# BTRelays.net
KiCad netlist of a schematic drawn in EAGLE
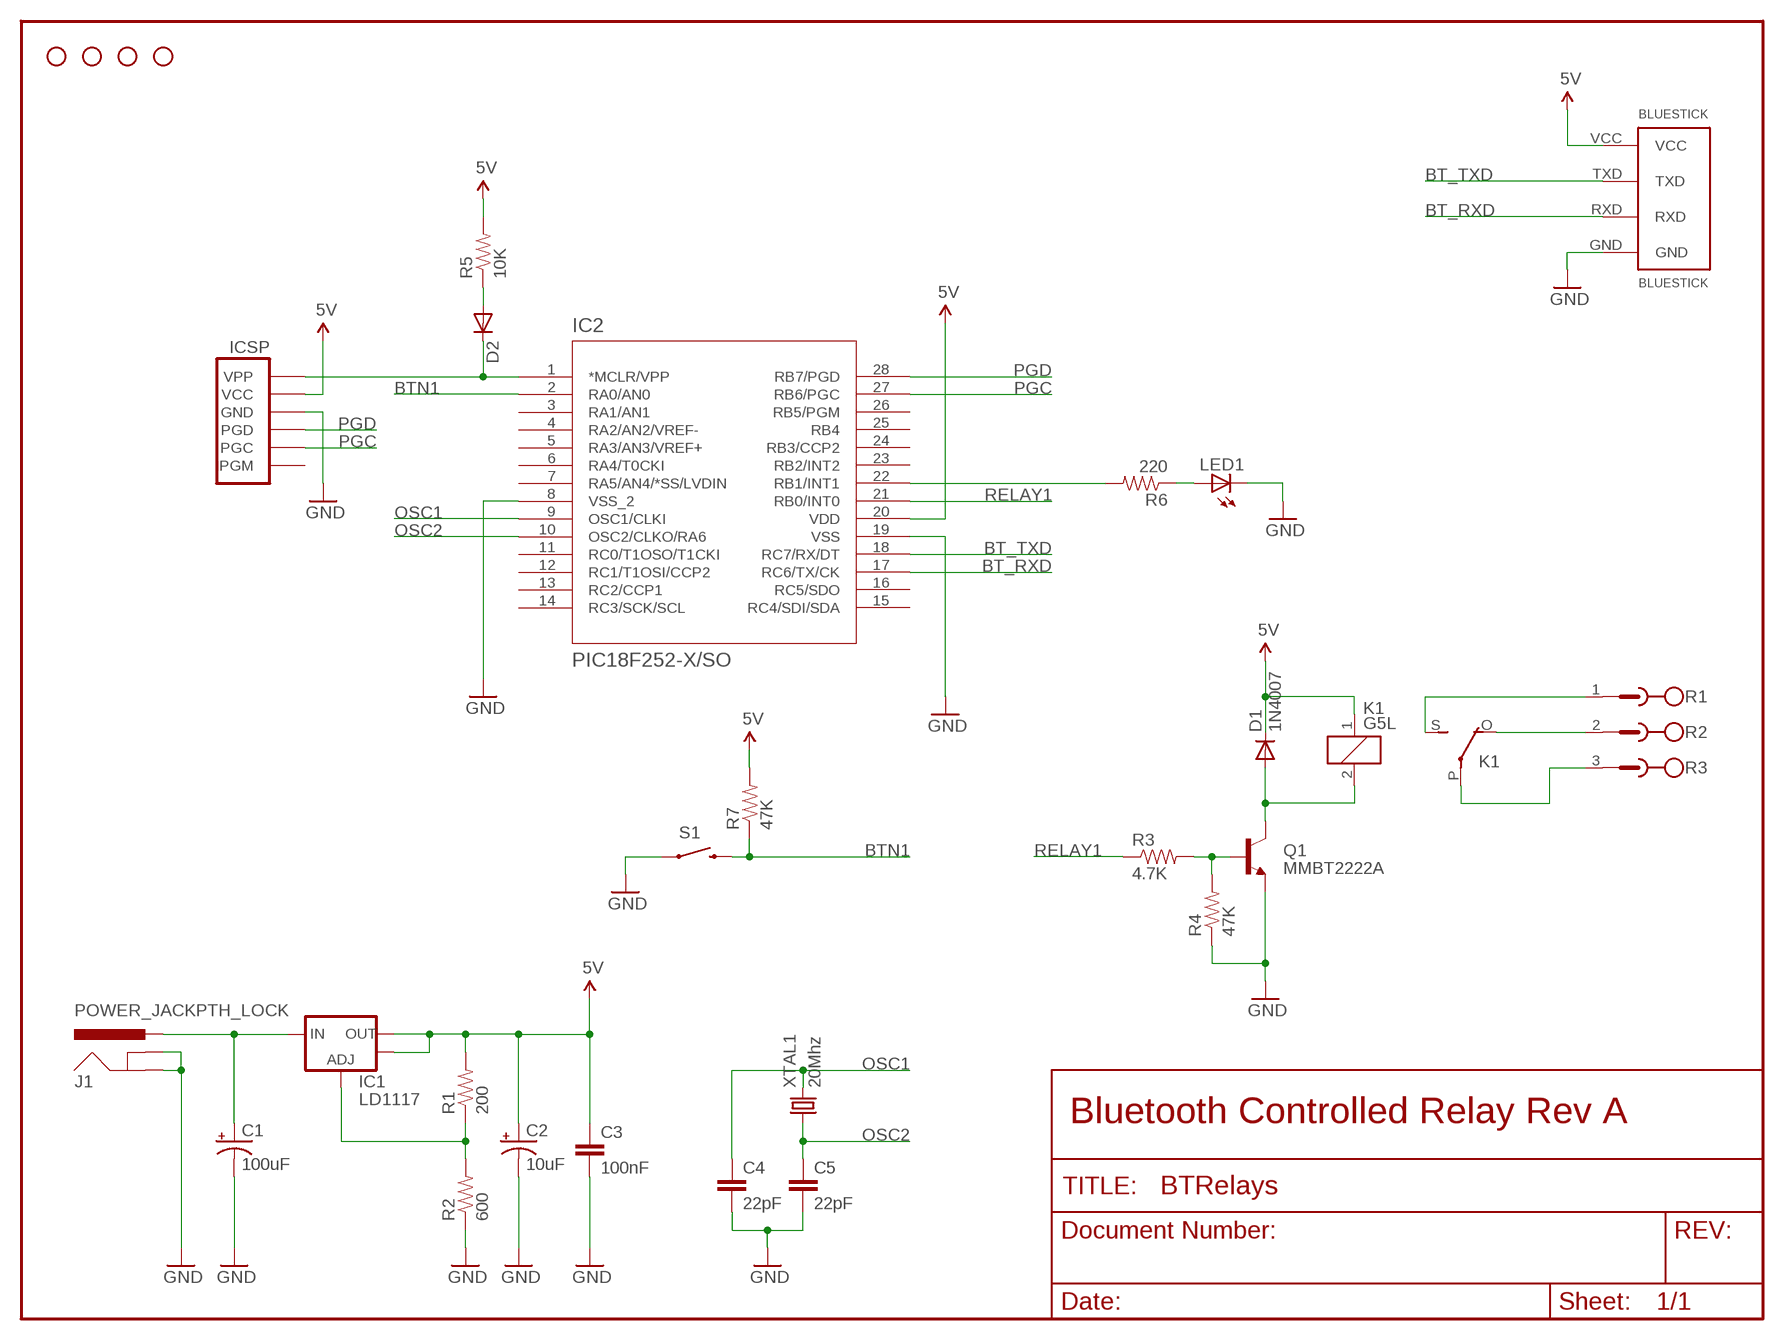
[diagram p0: schematic, sheet 1]

(export (version "E")
  (design (tool "Eeschema 10.0.6"))
  (components
    (comp (ref "BLUESTICK")
      (value "BLUESTICK")
      (footprint "eagle-import:BLUESTICK-PTH")
      (libsource (lib "eagle-import") (part "BLUESTICK"))
    )
    (comp (ref "C1")
      (value "100uF")
      (footprint "eagle-import:CPOL-RADIAL-100UF-25V")
      (libsource (lib "eagle-import") (part "CAP_POLPTH1"))
    )
    (comp (ref "C2")
      (value "10uF")
      (footprint "eagle-import:EIA3216")
      (libsource (lib "eagle-import") (part "CAP_POL1206"))
    )
    (comp (ref "C3")
      (value "100nF")
      (footprint "eagle-import:1206")
      (libsource (lib "eagle-import") (part "CAP1206"))
    )
    (comp (ref "C4")
      (value "22pF")
      (footprint "eagle-import:1206")
      (libsource (lib "eagle-import") (part "CAP1206"))
    )
    (comp (ref "C5")
      (value "22pF")
      (footprint "eagle-import:1206")
      (libsource (lib "eagle-import") (part "CAP1206"))
    )
    (comp (ref "D1")
      (value "1N4007")
      (footprint "eagle-import:DIODE-1N4001")
      (libsource (lib "eagle-import") (part "DIODEPTH"))
    )
    (comp (ref "D2")
      (value "DIODESMA")
      (footprint "eagle-import:SMA-DIODE")
      (libsource (lib "eagle-import") (part "DIODESMA"))
    )
    (comp (ref "IC1")
      (value "LD1117")
      (footprint "eagle-import:SOT223")
      (libsource (lib "eagle-import") (part "V_REG_LM1117SOT223"))
    )
    (comp (ref "IC2")
      (value "PIC18F252-X/SO")
      (footprint "eagle-import:SOIC28-W_MC")
      (libsource (lib "eagle-import") (part "PIC18F252-X/SO"))
    )
    (comp (ref "ICSP")
      (value "PIC-ICSPPOLAR_LOCK")
      (footprint "eagle-import:MOLEX-1X6_LOCK")
      (libsource (lib "eagle-import") (part "PIC-ICSPPOLAR_LOCK"))
    )
    (comp (ref "J1")
      (value "POWER_JACKPTH_LOCK")
      (footprint "eagle-import:POWER_JACK_PTH_LOCK")
      (libsource (lib "eagle-import") (part "POWER_JACKPTH_LOCK"))
    )
    (comp (ref "JP1")
      (value "STAND-OFF")
      (footprint "eagle-import:STAND-OFF")
      (libsource (lib "eagle-import") (part "STAND-OFF"))
    )
    (comp (ref "JP2")
      (value "STAND-OFF")
      (footprint "eagle-import:STAND-OFF")
      (libsource (lib "eagle-import") (part "STAND-OFF"))
    )
    (comp (ref "JP3")
      (value "STAND-OFF")
      (footprint "eagle-import:STAND-OFF")
      (libsource (lib "eagle-import") (part "STAND-OFF"))
    )
    (comp (ref "JP4")
      (value "STAND-OFF")
      (footprint "eagle-import:STAND-OFF")
      (libsource (lib "eagle-import") (part "STAND-OFF"))
    )
    (comp (ref "K1")
      (value "G5L")
      (footprint "eagle-import:G5LE")
      (libsource (lib "eagle-import") (part "G5L"))
    )
    (comp (ref "LED1")
      (value "LED1206")
      (footprint "eagle-import:LED-1206")
      (libsource (lib "eagle-import") (part "LED1206"))
    )
    (comp (ref "Q1")
      (value "MMBT2222A")
      (footprint "eagle-import:SOT23")
      (libsource (lib "eagle-import") (part "TRANSISTOR_NPNSOT23"))
    )
    (comp (ref "R")
      (value "MSTBV3")
      (footprint "eagle-import:MSTBV3")
      (libsource (lib "eagle-import") (part "MSTBV3"))
    )
    (comp (ref "R1")
      (value "200")
      (footprint "eagle-import:1206")
      (libsource (lib "eagle-import") (part "RESISTOR1206"))
    )
    (comp (ref "R2")
      (value "600")
      (footprint "eagle-import:1206")
      (libsource (lib "eagle-import") (part "RESISTOR1206"))
    )
    (comp (ref "R3")
      (value "4.7K")
      (footprint "eagle-import:1206")
      (libsource (lib "eagle-import") (part "RESISTOR1206"))
    )
    (comp (ref "R4")
      (value "47K")
      (footprint "eagle-import:1206")
      (libsource (lib "eagle-import") (part "RESISTOR1206"))
    )
    (comp (ref "R5")
      (value "10K")
      (footprint "eagle-import:1206")
      (libsource (lib "eagle-import") (part "RESISTOR1206"))
    )
    (comp (ref "R6")
      (value "220")
      (footprint "eagle-import:1206")
      (libsource (lib "eagle-import") (part "RESISTOR1206"))
    )
    (comp (ref "R7")
      (value "47K")
      (footprint "eagle-import:1206")
      (libsource (lib "eagle-import") (part "RESISTOR1206"))
    )
    (comp (ref "S1")
      (value "SWITCH-MOMENTARY-2SMD")
      (footprint "eagle-import:TACTILE_SWITCH_SMD")
      (libsource (lib "eagle-import") (part "SWITCH-MOMENTARY-2SMD"))
    )
    (comp (ref "XTAL1")
      (value "20Mhz")
      (footprint "eagle-import:HC49US")
      (libsource (lib "eagle-import") (part "CRYSTALHC49US"))
    )
  )
  (nets
    (net (code "1") (name "/BTN1") (class "Default")
      (node (ref "IC2") (pin "2") (pinfunction "RA0/AN0_2") (pintype "passive"))
      (node (ref "R7") (pin "1") (pinfunction "1_1") (pintype "passive"))
      (node (ref "S1") (pin "3") (pinfunction "2_3") (pintype "passive"))
    )
    (net (code "2") (name "/BT_RXD") (class "Default")
      (node (ref "BLUESTICK") (pin "RXD") (pinfunction "RXD_RXD") (pintype "bidirectional"))
      (node (ref "IC2") (pin "17") (pinfunction "RC6/TX/CK_17") (pintype "passive"))
    )
    (net (code "3") (name "/BT_TXD") (class "Default")
      (node (ref "BLUESTICK") (pin "TXD") (pinfunction "TXD_TXD") (pintype "bidirectional"))
      (node (ref "IC2") (pin "18") (pinfunction "RC7/RX/DT_18") (pintype "passive"))
    )
    (net (code "4") (name "/OSC1") (class "Default")
      (node (ref "C4") (pin "1") (pinfunction "1_1") (pintype "passive"))
      (node (ref "IC2") (pin "9") (pinfunction "OSC1/CLKI_9") (pintype "passive"))
      (node (ref "XTAL1") (pin "2") (pinfunction "2_2") (pintype "passive"))
    )
    (net (code "5") (name "/OSC2") (class "Default")
      (node (ref "C5") (pin "1") (pinfunction "1_1") (pintype "passive"))
      (node (ref "IC2") (pin "10") (pinfunction "OSC2/CLKO/RA6_10") (pintype "passive"))
      (node (ref "XTAL1") (pin "1") (pinfunction "1_1") (pintype "passive"))
    )
    (net (code "6") (name "/PGC") (class "Default")
      (node (ref "IC2") (pin "27") (pinfunction "RB6/PGC_27") (pintype "passive"))
      (node (ref "ICSP") (pin "2") (pinfunction "PGC_2") (pintype "bidirectional"))
    )
    (net (code "7") (name "/PGD") (class "Default")
      (node (ref "IC2") (pin "28") (pinfunction "RB7/PGD_28") (pintype "passive"))
      (node (ref "ICSP") (pin "3") (pinfunction "PGD_3") (pintype "bidirectional"))
    )
    (net (code "8") (name "/RELAY1") (class "Default")
      (node (ref "IC2") (pin "21") (pinfunction "RB0/INT0_21") (pintype "passive"))
      (node (ref "R3") (pin "1") (pinfunction "1_1") (pintype "passive"))
    )
    (net (code "9") (name "5V") (class "Default")
      (node (ref "BLUESTICK") (pin "VCC") (pinfunction "VCC_VCC") (pintype "bidirectional"))
      (node (ref "C2") (pin "A") (pinfunction "+_A") (pintype "passive"))
      (node (ref "C3") (pin "1") (pinfunction "1_1") (pintype "passive"))
      (node (ref "D1") (pin "C") (pinfunction "C_C") (pintype "passive"))
      (node (ref "IC1") (pin "2") (pinfunction "OUT_2") (pintype "output"))
      (node (ref "IC1") (pin "4") (pinfunction "OUT_4") (pintype "output"))
      (node (ref "IC2") (pin "20") (pinfunction "VDD_20") (pintype "passive"))
      (node (ref "ICSP") (pin "5") (pinfunction "VCC_5") (pintype "bidirectional"))
      (node (ref "K1") (pin "1") (pinfunction "1_1") (pintype "passive"))
      (node (ref "R1") (pin "2") (pinfunction "2_2") (pintype "passive"))
      (node (ref "R5") (pin "2") (pinfunction "2_2") (pintype "passive"))
      (node (ref "R7") (pin "2") (pinfunction "2_2") (pintype "passive"))
    )
    (net (code "10") (name "GND") (class "Default")
      (node (ref "BLUESTICK") (pin "GND") (pinfunction "GND_GND") (pintype "bidirectional"))
      (node (ref "C1") (pin "2") (pinfunction "-_2") (pintype "passive"))
      (node (ref "C2") (pin "C") (pinfunction "-_C") (pintype "passive"))
      (node (ref "C3") (pin "2") (pinfunction "2_2") (pintype "passive"))
      (node (ref "C4") (pin "2") (pinfunction "2_2") (pintype "passive"))
      (node (ref "C5") (pin "2") (pinfunction "2_2") (pintype "passive"))
      (node (ref "IC2") (pin "19") (pinfunction "VSS_19") (pintype "passive"))
      (node (ref "IC2") (pin "8") (pinfunction "VSS_2_8") (pintype "passive"))
      (node (ref "ICSP") (pin "4") (pinfunction "GND_4") (pintype "bidirectional"))
      (node (ref "J1") (pin "GND") (pinfunction "GND_GND") (pintype "bidirectional"))
      (node (ref "J1") (pin "GNDBREAK") (pinfunction "GNDBREAK_GNDBREAK") (pintype "bidirectional"))
      (node (ref "LED1") (pin "C") (pinfunction "C_C") (pintype "passive"))
      (node (ref "Q1") (pin "2") (pinfunction "E_2") (pintype "passive"))
      (node (ref "R2") (pin "1") (pinfunction "1_1") (pintype "passive"))
      (node (ref "R4") (pin "1") (pinfunction "1_1") (pintype "passive"))
      (node (ref "S1") (pin "1") (pinfunction "1_1") (pintype "passive"))
    )
    (net (code "11") (name "Net-(C1-+)") (class "Default")
      (node (ref "C1") (pin "1") (pinfunction "+_1") (pintype "passive"))
      (node (ref "IC1") (pin "3") (pinfunction "IN_3") (pintype "input"))
      (node (ref "J1") (pin "PWR") (pinfunction "PWR_PWR") (pintype "bidirectional"))
    )
    (net (code "12") (name "Net-(D2-PadA)") (class "Default")
      (node (ref "D2") (pin "A") (pinfunction "A_A") (pintype "passive"))
      (node (ref "R5") (pin "1") (pinfunction "1_1") (pintype "passive"))
    )
    (net (code "13") (name "Net-(IC1-ADJ)") (class "Default")
      (node (ref "IC1") (pin "1") (pinfunction "ADJ_1") (pintype "input"))
      (node (ref "R1") (pin "1") (pinfunction "1_1") (pintype "passive"))
      (node (ref "R2") (pin "2") (pinfunction "2_2") (pintype "passive"))
    )
    (net (code "14") (name "Net-(IC2-*MCLR{slash}VPP)") (class "Default")
      (node (ref "D2") (pin "C") (pinfunction "C_C") (pintype "passive"))
      (node (ref "IC2") (pin "1") (pinfunction "*MCLR/VPP_1") (pintype "passive"))
      (node (ref "ICSP") (pin "6") (pinfunction "VPP_6") (pintype "bidirectional"))
    )
    (net (code "15") (name "Net-(IC2-RB1{slash}INT1)") (class "Default")
      (node (ref "IC2") (pin "22") (pinfunction "RB1/INT1_22") (pintype "passive"))
      (node (ref "R6") (pin "2") (pinfunction "2_2") (pintype "passive"))
    )
    (net (code "16") (name "Net-(LED1-PadA)") (class "Default")
      (node (ref "LED1") (pin "A") (pinfunction "A_A") (pintype "passive"))
      (node (ref "R6") (pin "1") (pinfunction "1_1") (pintype "passive"))
    )
    (net (code "17") (name "Net-(Q1-B)") (class "Default")
      (node (ref "Q1") (pin "1") (pinfunction "B_1") (pintype "passive"))
      (node (ref "R3") (pin "2") (pinfunction "2_2") (pintype "passive"))
      (node (ref "R4") (pin "2") (pinfunction "2_2") (pintype "passive"))
    )
    (net (code "18") (name "Net-(Q1-C)") (class "Default")
      (node (ref "D1") (pin "A") (pinfunction "A_A") (pintype "passive"))
      (node (ref "K1") (pin "2") (pinfunction "2_2") (pintype "passive"))
      (node (ref "Q1") (pin "3") (pinfunction "C_3") (pintype "passive"))
    )
    (net (code "19") (name "Net-(RA-SK)") (class "Default")
      (node (ref "K1") (pin "S") (pinfunction "S_S") (pintype "passive"))
      (node (ref "R") (pin "1") (pinfunction "SK_1") (pintype "passive"))
    )
    (net (code "20") (name "Net-(RB-SK)") (class "Default")
      (node (ref "K1") (pin "O") (pinfunction "O_O") (pintype "passive"))
      (node (ref "R") (pin "2") (pinfunction "SK_2") (pintype "passive"))
    )
    (net (code "21") (name "Net-(RC-SK)") (class "Default")
      (node (ref "K1") (pin "P") (pinfunction "P_P") (pintype "passive"))
      (node (ref "R") (pin "3") (pinfunction "SK_3") (pintype "passive"))
    )
    (net (code "22") (name "unconnected-(IC2-RA1{slash}AN1-Pad3)") (class "Default")
      (node (ref "IC2") (pin "3") (pinfunction "RA1/AN1_3") (pintype "passive"))
    )
    (net (code "23") (name "unconnected-(IC2-RA2{slash}AN2{slash}VREF--Pad4)") (class "Default")
      (node (ref "IC2") (pin "4") (pinfunction "RA2/AN2/VREF-_4") (pintype "passive"))
    )
    (net (code "24") (name "unconnected-(IC2-RA3{slash}AN3{slash}VREF+-Pad5)") (class "Default")
      (node (ref "IC2") (pin "5") (pinfunction "RA3/AN3/VREF+_5") (pintype "passive"))
    )
    (net (code "25") (name "unconnected-(IC2-RA4{slash}T0CKI-Pad6)") (class "Default")
      (node (ref "IC2") (pin "6") (pinfunction "RA4/T0CKI_6") (pintype "passive"))
    )
    (net (code "26") (name "unconnected-(IC2-RA5{slash}AN4{slash}*SS{slash}LVDIN-Pad7)") (class "Default")
      (node (ref "IC2") (pin "7") (pinfunction "RA5/AN4/*SS/LVDIN_7") (pintype "passive"))
    )
    (net (code "27") (name "unconnected-(IC2-RB2{slash}INT2-Pad23)") (class "Default")
      (node (ref "IC2") (pin "23") (pinfunction "RB2/INT2_23") (pintype "passive"))
    )
    (net (code "28") (name "unconnected-(IC2-RB3{slash}CCP2-Pad24)") (class "Default")
      (node (ref "IC2") (pin "24") (pinfunction "RB3/CCP2_24") (pintype "passive"))
    )
    (net (code "29") (name "unconnected-(IC2-RB4-Pad25)") (class "Default")
      (node (ref "IC2") (pin "25") (pinfunction "RB4_25") (pintype "passive"))
    )
    (net (code "30") (name "unconnected-(IC2-RB5{slash}PGM-Pad26)") (class "Default")
      (node (ref "IC2") (pin "26") (pinfunction "RB5/PGM_26") (pintype "passive"))
    )
    (net (code "31") (name "unconnected-(IC2-RC0{slash}T1OSO{slash}T1CKI-Pad11)") (class "Default")
      (node (ref "IC2") (pin "11") (pinfunction "RC0/T1OSO/T1CKI_11") (pintype "passive"))
    )
    (net (code "32") (name "unconnected-(IC2-RC1{slash}T1OSI{slash}CCP2-Pad12)") (class "Default")
      (node (ref "IC2") (pin "12") (pinfunction "RC1/T1OSI/CCP2_12") (pintype "passive"))
    )
    (net (code "33") (name "unconnected-(IC2-RC2{slash}CCP1-Pad13)") (class "Default")
      (node (ref "IC2") (pin "13") (pinfunction "RC2/CCP1_13") (pintype "passive"))
    )
    (net (code "34") (name "unconnected-(IC2-RC3{slash}SCK{slash}SCL-Pad14)") (class "Default")
      (node (ref "IC2") (pin "14") (pinfunction "RC3/SCK/SCL_14") (pintype "passive"))
    )
    (net (code "35") (name "unconnected-(IC2-RC4{slash}SDI{slash}SDA-Pad15)") (class "Default")
      (node (ref "IC2") (pin "15") (pinfunction "RC4/SDI/SDA_15") (pintype "passive"))
    )
    (net (code "36") (name "unconnected-(IC2-RC5{slash}SDO-Pad16)") (class "Default")
      (node (ref "IC2") (pin "16") (pinfunction "RC5/SDO_16") (pintype "passive"))
    )
    (net (code "37") (name "unconnected-(ICSP-PGM-Pad1)") (class "Default")
      (node (ref "ICSP") (pin "1") (pinfunction "PGM_1") (pintype "bidirectional"))
    )
  )
)
